# WS281x.net
KiCad netlist of a schematic drawn in Altium Designer
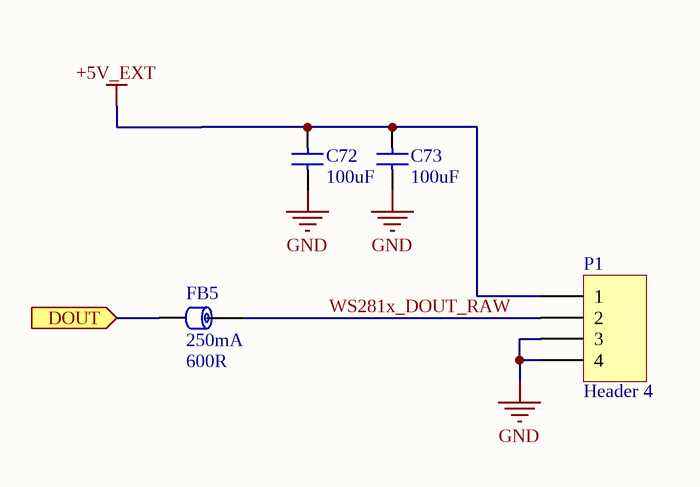
[diagram p0: WS281x.SchDoc]

(export (version "E")
  (design (tool "Eeschema 10.0.6"))
  (components
    (comp (ref "C72")
      (value "100uF")
      (footprint "1210_Capacitor")
      (description "CAP CER 100UF 6.3V 20% X5R 1210")
      (fields (field (name "Comment") "C3225X5R0J107M250AC") (field (name "SVP CREATOR") "Spencer Berglund"))
      (libsource (lib "capacitor") (part "C_1210_100uF_6.3V_20%"))
    )
    (comp (ref "C73")
      (value "100uF")
      (footprint "1210_Capacitor")
      (description "CAP CER 100UF 6.3V 20% X5R 1210")
      (fields (field (name "Comment") "C3225X5R0J107M250AC") (field (name "SVP CREATOR") "Spencer Berglund"))
      (libsource (lib "capacitor") (part "C_1210_100uF_6.3V_20%"))
    )
    (comp (ref "FB5")
      (value "600R")
      (footprint "0402_Inductor")
      (description "600 Ohms @ 100MHz 1 Ferrite Bead 0402 (1005 Metric) 250mA 500mOhm")
      (fields
        (field (name "MANUFACTURER") "Taiyo Yuden")
        (field (name "MANUFACTURER PART NUMBER") "BK1005HM601-T")
        (field (name "CURRENT RATING") "250mA")
      )
      (libsource (lib "inductor") (part "FB_0402_600R_250mA"))
    )
    (comp (ref "P1")
      (value "Header 4")
      (footprint "HDR1X4")
      (description "Header, 4-Pin")
      (fields (field (name "PUBLISHER") "Altium Limited"))
      (libsource (lib "Miscellaneous Connectors") (part "Header 4"))
    )
  )
  (nets
    (net (code "1") (name "+5V_EXT") (class "Default")
      (node (ref "C72") (pin "1") (pinfunction "1_1") (pintype "passive"))
      (node (ref "C73") (pin "1") (pinfunction "1_1") (pintype "passive"))
      (node (ref "P1") (pin "1") (pinfunction "1_1") (pintype "passive"))
    )
    (net (code "2") (name "/DOUT") (class "Default")
      (node (ref "FB5") (pin "1") (pinfunction "1_1") (pintype "passive"))
    )
    (net (code "3") (name "/WS281x_DOUT_RAW") (class "Default")
      (node (ref "FB5") (pin "2") (pinfunction "2_2") (pintype "passive"))
      (node (ref "P1") (pin "2") (pinfunction "2_2") (pintype "passive"))
    )
    (net (code "4") (name "GND") (class "Default")
      (node (ref "C72") (pin "2") (pinfunction "2_2") (pintype "passive"))
      (node (ref "C73") (pin "2") (pinfunction "2_2") (pintype "passive"))
      (node (ref "P1") (pin "3") (pinfunction "3_3") (pintype "passive"))
      (node (ref "P1") (pin "4") (pinfunction "4_4") (pintype "passive"))
    )
  )
)
